# PaxGeo_HallBoard.net
KiCad netlist of a schematic drawn in EAGLE
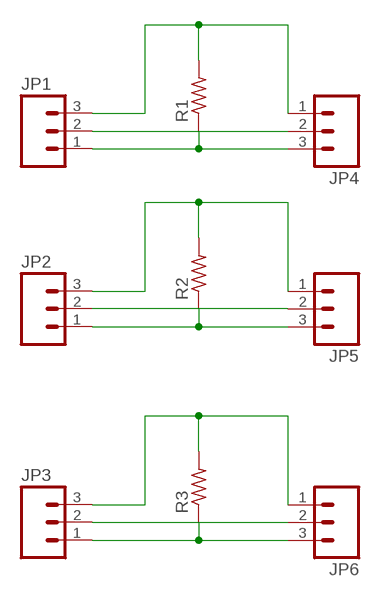
[diagram p0: schematic, sheet 1]

(export (version "E")
  (design (tool "Eeschema 10.0.6"))
  (components
    (comp (ref "JP1")
      (value "M03SCREW")
      (footprint "eagle-import:SCREWTERMINAL-3.5MM-3")
      (libsource (lib "eagle-import") (part "M03SCREW"))
    )
    (comp (ref "JP2")
      (value "M03SCREW")
      (footprint "eagle-import:SCREWTERMINAL-3.5MM-3")
      (libsource (lib "eagle-import") (part "M03SCREW"))
    )
    (comp (ref "JP3")
      (value "M03SCREW")
      (footprint "eagle-import:SCREWTERMINAL-3.5MM-3")
      (libsource (lib "eagle-import") (part "M03SCREW"))
    )
    (comp (ref "JP4")
      (value "M03SCREW")
      (footprint "eagle-import:SCREWTERMINAL-3.5MM-3")
      (libsource (lib "eagle-import") (part "M03SCREW"))
    )
    (comp (ref "JP5")
      (value "M03SCREW")
      (footprint "eagle-import:SCREWTERMINAL-3.5MM-3")
      (libsource (lib "eagle-import") (part "M03SCREW"))
    )
    (comp (ref "JP6")
      (value "M03SCREW")
      (footprint "eagle-import:SCREWTERMINAL-3.5MM-3")
      (libsource (lib "eagle-import") (part "M03SCREW"))
    )
    (comp (ref "R1")
      (value "R-US_0204/7")
      (footprint "eagle-import:0204_7")
      (libsource (lib "eagle-import") (part "R-US_0204/7"))
    )
    (comp (ref "R2")
      (value "R-US_0204/7")
      (footprint "eagle-import:0204_7")
      (libsource (lib "eagle-import") (part "R-US_0204/7"))
    )
    (comp (ref "R3")
      (value "R-US_0204/7")
      (footprint "eagle-import:0204_7")
      (libsource (lib "eagle-import") (part "R-US_0204/7"))
    )
  )
  (nets
    (net (code "1") (name "Net-(JP1-Pad1)") (class "Default")
      (node (ref "JP1") (pin "1") (pinfunction "1_1") (pintype "passive"))
      (node (ref "JP4") (pin "3") (pinfunction "3_3") (pintype "passive"))
      (node (ref "R1") (pin "1") (pinfunction "1_1") (pintype "passive"))
    )
    (net (code "2") (name "Net-(JP1-Pad2)") (class "Default")
      (node (ref "JP1") (pin "2") (pinfunction "2_2") (pintype "passive"))
      (node (ref "JP4") (pin "2") (pinfunction "2_2") (pintype "passive"))
    )
    (net (code "3") (name "Net-(JP1-Pad3)") (class "Default")
      (node (ref "JP1") (pin "3") (pinfunction "3_3") (pintype "passive"))
      (node (ref "JP4") (pin "1") (pinfunction "1_1") (pintype "passive"))
      (node (ref "R1") (pin "2") (pinfunction "2_2") (pintype "passive"))
    )
    (net (code "4") (name "Net-(JP2-Pad1)") (class "Default")
      (node (ref "JP2") (pin "1") (pinfunction "1_1") (pintype "passive"))
      (node (ref "JP5") (pin "3") (pinfunction "3_3") (pintype "passive"))
      (node (ref "R2") (pin "1") (pinfunction "1_1") (pintype "passive"))
    )
    (net (code "5") (name "Net-(JP2-Pad2)") (class "Default")
      (node (ref "JP2") (pin "2") (pinfunction "2_2") (pintype "passive"))
      (node (ref "JP5") (pin "2") (pinfunction "2_2") (pintype "passive"))
    )
    (net (code "6") (name "Net-(JP2-Pad3)") (class "Default")
      (node (ref "JP2") (pin "3") (pinfunction "3_3") (pintype "passive"))
      (node (ref "JP5") (pin "1") (pinfunction "1_1") (pintype "passive"))
      (node (ref "R2") (pin "2") (pinfunction "2_2") (pintype "passive"))
    )
    (net (code "7") (name "Net-(JP3-Pad1)") (class "Default")
      (node (ref "JP3") (pin "1") (pinfunction "1_1") (pintype "passive"))
      (node (ref "JP6") (pin "3") (pinfunction "3_3") (pintype "passive"))
      (node (ref "R3") (pin "1") (pinfunction "1_1") (pintype "passive"))
    )
    (net (code "8") (name "Net-(JP3-Pad2)") (class "Default")
      (node (ref "JP3") (pin "2") (pinfunction "2_2") (pintype "passive"))
      (node (ref "JP6") (pin "2") (pinfunction "2_2") (pintype "passive"))
    )
    (net (code "9") (name "Net-(JP3-Pad3)") (class "Default")
      (node (ref "JP3") (pin "3") (pinfunction "3_3") (pintype "passive"))
      (node (ref "JP6") (pin "1") (pinfunction "1_1") (pintype "passive"))
      (node (ref "R3") (pin "2") (pinfunction "2_2") (pintype "passive"))
    )
  )
)
